# Copy_of_5V_Buck.net
KiCad netlist of a schematic drawn in Altium Designer
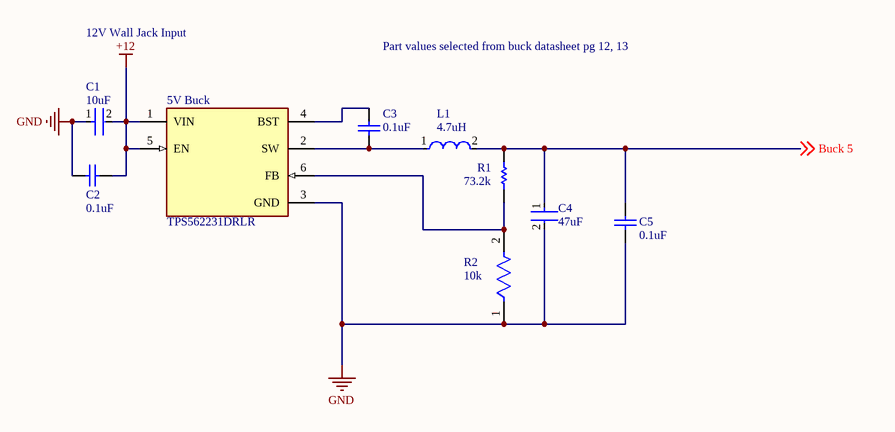
[diagram p0: Copy of 5V Buck.SchDoc]

(export (version "E")
  (design (tool "Eeschema 10.0.6"))
  (components
    (comp (ref "5V Buck")
      (value "TPS562231DRLR")
      (footprint "FP-DRL0006A-MFG")
      (description "POWER MANAGEMENT")
      (libsource (lib "Altium Content Vault") (part "11aae5693f510e0d396f49b7d198f22"))
    )
    (comp (ref "C1")
      (value "10uF")
      (footprint "FP-CL21-IPC_B")
      (description "CL21 Series 0805 10uF 25V ±10% Tolerance X5R Multilayer Ceramic Chip Capacitor")
      (fields (field (name "CAPACITANCE") "10uF") (field (name "TOLERANCE") "10%"))
      (libsource (lib "Altium Content Vault") (part "b4654b650e69147ec39a6b967a45e02"))
    )
    (comp (ref "C2")
      (value "0.1uF")
      (footprint "CAPC2013X94X50LL20T25")
      (fields
        (field (name "PART NUMBER") "08055C104JAT4A")
        (field (name "MANUFACTURER") "AVX Interconnect / Elco")
      )
      (libsource (lib "Altium Content Vault") (part "CAP"))
    )
    (comp (ref "C3")
      (value "0.1uF")
      (footprint "CAPC2013X94X50LL20T25")
      (fields
        (field (name "PART NUMBER") "08055C104JAT4A")
        (field (name "MANUFACTURER") "AVX Interconnect / Elco")
      )
      (libsource (lib "Altium Content Vault") (part "CAP"))
    )
    (comp (ref "C4")
      (value "47uF")
      (footprint "FP-C3216-160-0_2-MFG")
      (description "Multilayer Ceramic Capacitors 47uF ±20% 25V X5R SMD 1206")
      (fields (field (name "VOLTAGE") "25V") (field (name "TOLERANCE") "20%"))
      (libsource (lib "Altium Content Vault") (part "11868f565c42a9108669ba33697ecf6"))
    )
    (comp (ref "C5")
      (value "0.1uF")
      (footprint "CAPC2013X94X50LL20T25")
      (fields
        (field (name "PART NUMBER") "08055C104JAT4A")
        (field (name "MANUFACTURER") "AVX Interconnect / Elco")
      )
      (libsource (lib "Altium Content Vault") (part "CAP"))
    )
    (comp (ref "L1")
      (value "4.7uH")
      (footprint "FP-NR8040-H_4_2-MFG")
      (description "Shielded Wirewound Inductor 4.7uH 30% 4.1A 23.4mΩ SMD")
      (fields (field (name "TOLERANCE") "30%"))
      (libsource (lib "Altium Content Vault") (part "725321dda6339637d4d059423bc1c3c"))
    )
    (comp (ref "R1")
      (value "73.2k")
      (footprint "RESC1609X50X30NL10T20")
      (fields (field (name "MANUFACTURER") "Vishay Dale") (field (name "PART NUMBER") "CRCW060373K2FKEA"))
      (libsource (lib "Altium Content Vault") (part "RES"))
    )
    (comp (ref "R2")
      (value "10k")
      (footprint "FP-RK73H1J-IPC_B")
      (description "10kΩ ±1% 0.1W Chip Resistor 0603 Thick Film AEC-Q200 Qualified")
      (fields (field (name "TOLERANCE") "1%"))
      (libsource (lib "Altium Content Vault") (part "1029c3af85768c4190bb7ad29bc67b5"))
    )
  )
  (nets
    (net (code "1") (name "+12") (class "Default")
      (node (ref "5V Buck") (pin "1") (pinfunction "VIN_1") (pintype "power_in"))
      (node (ref "5V Buck") (pin "5") (pinfunction "EN_5") (pintype "input"))
      (node (ref "C1") (pin "2") (pinfunction "2_2") (pintype "passive"))
      (node (ref "C2") (pin "2") (pinfunction "2_2") (pintype "passive"))
    )
    (net (code "2") (name "Buck 5") (class "Default")
      (node (ref "C4") (pin "1") (pinfunction "1_1") (pintype "passive"))
      (node (ref "C5") (pin "2") (pinfunction "2_2") (pintype "passive"))
      (node (ref "L1") (pin "2") (pinfunction "2_2") (pintype "passive"))
      (node (ref "R1") (pin "2") (pinfunction "2_2") (pintype "passive"))
    )
    (net (code "3") (name "GND") (class "Default")
      (node (ref "5V Buck") (pin "3") (pinfunction "GND_3") (pintype "power_in"))
      (node (ref "C1") (pin "1") (pinfunction "1_1") (pintype "passive"))
      (node (ref "C2") (pin "1") (pinfunction "1_1") (pintype "passive"))
      (node (ref "C4") (pin "2") (pinfunction "2_2") (pintype "passive"))
      (node (ref "C5") (pin "1") (pinfunction "1_1") (pintype "passive"))
      (node (ref "R2") (pin "1") (pinfunction "1_1") (pintype "passive"))
    )
    (net (code "4") (name "Net-(5V Buck-BST)") (class "Default")
      (node (ref "5V Buck") (pin "4") (pinfunction "BST_4") (pintype "passive"))
      (node (ref "C3") (pin "2") (pinfunction "2_2") (pintype "passive"))
    )
    (net (code "5") (name "Net-(5V Buck-FB)") (class "Default")
      (node (ref "5V Buck") (pin "6") (pinfunction "FB_6") (pintype "input"))
      (node (ref "R1") (pin "1") (pinfunction "1_1") (pintype "passive"))
      (node (ref "R2") (pin "2") (pinfunction "2_2") (pintype "passive"))
    )
    (net (code "6") (name "Net-(5V Buck-SW)") (class "Default")
      (node (ref "5V Buck") (pin "2") (pinfunction "SW_2") (pintype "passive"))
      (node (ref "C3") (pin "1") (pinfunction "1_1") (pintype "passive"))
      (node (ref "L1") (pin "1") (pinfunction "1_1") (pintype "passive"))
    )
  )
)
